# USB-C_Power_Supply.net
KiCad netlist of a schematic drawn in Altium Designer
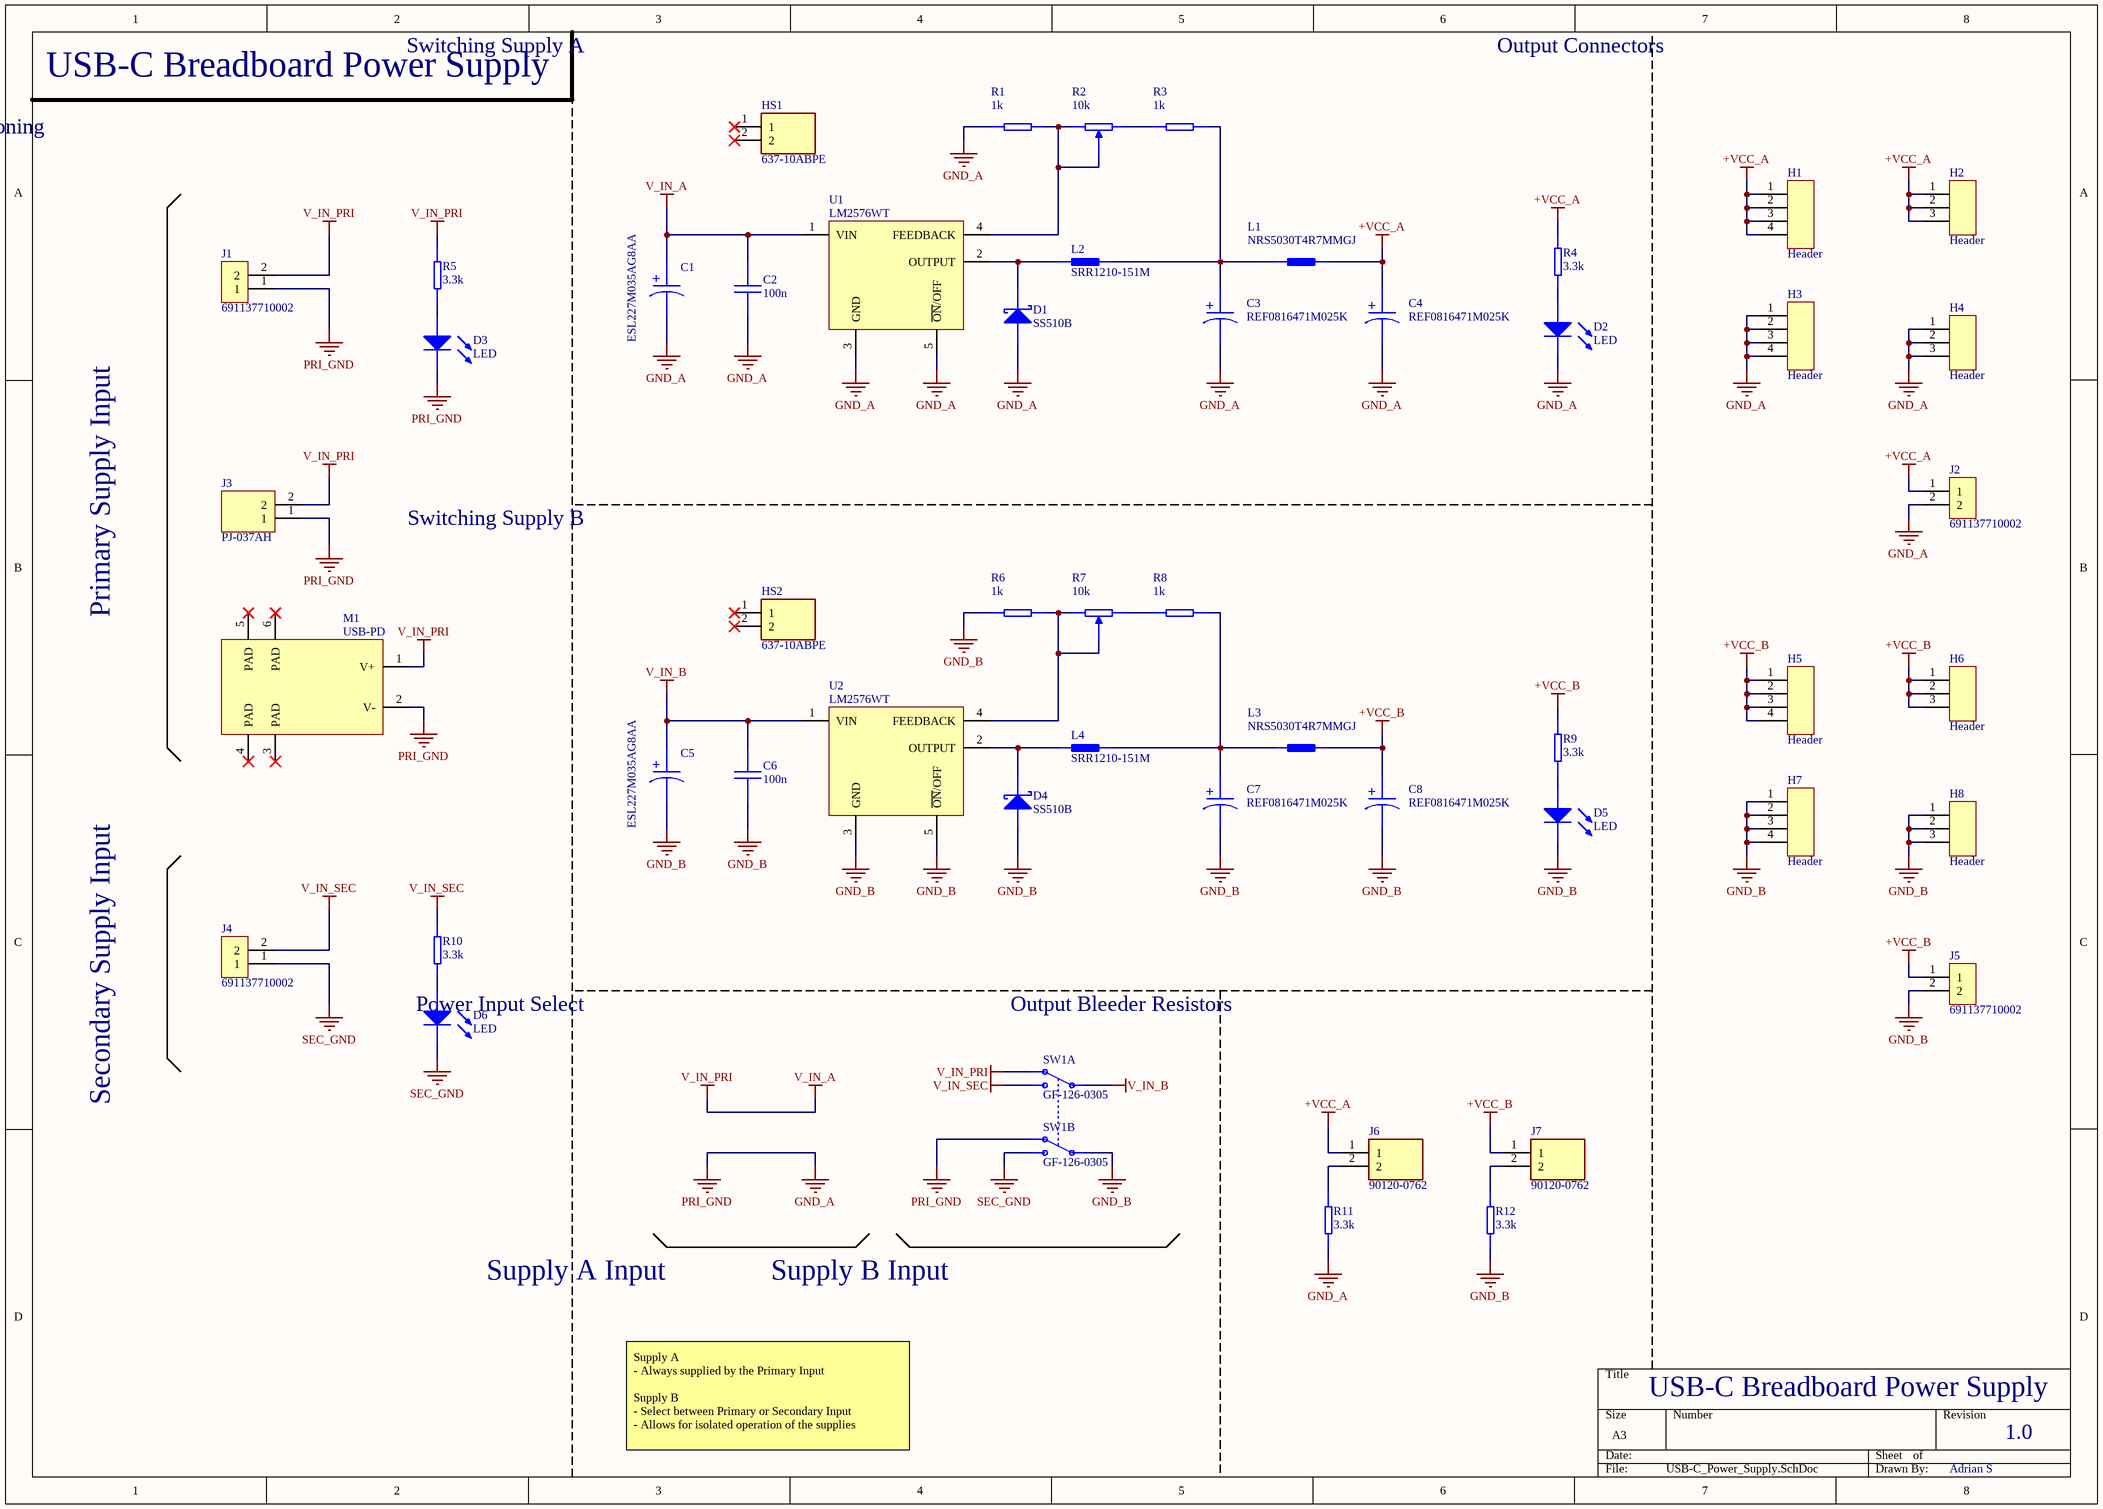
[diagram p0: USB-C_Power_Supply.SchDoc]

(export (version "E")
  (design (tool "Eeschema 10.0.6"))
  (components
    (comp (ref "C1")
      (value "ESL227M035AG8AA")
      (footprint "CAPTH8.00X18.00-3.50")
      (description "Capacitor Polarised")
      (fields (field (name "MOUSER PART NUMBER") "80-ESL227M035AG8AA"))
      (libsource (lib "TD") (part "ESL227M035AG8AA"))
    )
    (comp (ref "C2")
      (value "100n")
      (footprint "CAP0805")
      (description "Non Polarized Capacitor")
      (libsource (lib "TD") (part "Capacitor - Non Polarized"))
    )
    (comp (ref "C3")
      (value "REF0816471M025K")
      (footprint "CAPTH8.00X16.00-3.50")
      (description "Capacitor Polarised")
      (fields (field (name "MOUSER PART NUMBER") "581-REF0816471M025K"))
      (libsource (lib "TD") (part "REF0816471M025K"))
    )
    (comp (ref "C4")
      (value "REF0816471M025K")
      (footprint "CAPTH8.00X16.00-3.50")
      (description "Capacitor Polarised")
      (fields (field (name "MOUSER PART NUMBER") "581-REF0816471M025K"))
      (libsource (lib "TD") (part "REF0816471M025K"))
    )
    (comp (ref "C5")
      (value "ESL227M035AG8AA")
      (footprint "CAPTH8.00X18.00-3.50")
      (description "Capacitor Polarised")
      (fields (field (name "MOUSER PART NUMBER") "80-ESL227M035AG8AA"))
      (libsource (lib "TD") (part "ESL227M035AG8AA"))
    )
    (comp (ref "C6")
      (value "100n")
      (footprint "CAP0805")
      (description "Non Polarized Capacitor")
      (libsource (lib "TD") (part "Capacitor - Non Polarized"))
    )
    (comp (ref "C7")
      (value "REF0816471M025K")
      (footprint "CAPTH8.00X16.00-3.50")
      (description "Capacitor Polarised")
      (fields (field (name "MOUSER PART NUMBER") "581-REF0816471M025K"))
      (libsource (lib "TD") (part "REF0816471M025K"))
    )
    (comp (ref "C8")
      (value "REF0816471M025K")
      (footprint "CAPTH8.00X16.00-3.50")
      (description "Capacitor Polarised")
      (fields (field (name "MOUSER PART NUMBER") "581-REF0816471M025K"))
      (libsource (lib "TD") (part "REF0816471M025K"))
    )
    (comp (ref "D1")
      (value "SS510B")
      (footprint "DO-214AC (SMA)")
      (description "Diode")
      (libsource (lib "TD") (part "SS510B"))
    )
    (comp (ref "D2")
      (value "LED")
      (footprint "LEDM2012X80N")
      (description "General Purpose LED")
      (libsource (lib "TD") (part "LED"))
    )
    (comp (ref "D3")
      (value "LED")
      (footprint "LEDM2012X80N")
      (description "General Purpose LED")
      (libsource (lib "TD") (part "LED"))
    )
    (comp (ref "D4")
      (value "SS510B")
      (footprint "DO-214AC (SMA)")
      (description "Diode")
      (libsource (lib "TD") (part "SS510B"))
    )
    (comp (ref "D5")
      (value "LED")
      (footprint "LEDM2012X80N")
      (description "General Purpose LED")
      (libsource (lib "TD") (part "LED"))
    )
    (comp (ref "D6")
      (value "LED")
      (footprint "LEDM2012X80N")
      (description "General Purpose LED")
      (libsource (lib "TD") (part "LED"))
    )
    (comp (ref "H1")
      (value "Header")
      (footprint "Header_1X4")
      (description "4-Pin Header")
      (libsource (lib "TD") (part "4-Pin Header"))
    )
    (comp (ref "H2")
      (value "Header")
      (footprint "Header_1X3")
      (description "3-Pin Header")
      (libsource (lib "TD") (part "3-Pin Header"))
    )
    (comp (ref "H3")
      (value "Header")
      (footprint "Header_1X4")
      (description "4-Pin Header")
      (libsource (lib "TD") (part "4-Pin Header"))
    )
    (comp (ref "H4")
      (value "Header")
      (footprint "Header_1X3")
      (description "3-Pin Header")
      (libsource (lib "TD") (part "3-Pin Header"))
    )
    (comp (ref "H5")
      (value "Header")
      (footprint "Header_1X4")
      (description "4-Pin Header")
      (libsource (lib "TD") (part "4-Pin Header"))
    )
    (comp (ref "H6")
      (value "Header")
      (footprint "Header_1X3")
      (description "3-Pin Header")
      (libsource (lib "TD") (part "3-Pin Header"))
    )
    (comp (ref "H7")
      (value "Header")
      (footprint "Header_1X4")
      (description "4-Pin Header")
      (libsource (lib "TD") (part "4-Pin Header"))
    )
    (comp (ref "H8")
      (value "Header")
      (footprint "Header_1X3")
      (description "3-Pin Header")
      (libsource (lib "TD") (part "3-Pin Header"))
    )
    (comp (ref "HS1")
      (value "637-10ABPE")
      (footprint "63710ABPE")
      (description "Undefined or Miscellaneous")
      (fields (field (name "MOUSER PART NUMBER") "567-637-10ABPE"))
      (libsource (lib "*") (part "637-10ABPE"))
    )
    (comp (ref "HS2")
      (value "637-10ABPE")
      (footprint "63710ABPE")
      (description "Undefined or Miscellaneous")
      (fields (field (name "MOUSER PART NUMBER") "567-637-10ABPE"))
      (libsource (lib "*") (part "637-10ABPE"))
    )
    (comp (ref "J1")
      (value "691137710002")
      (footprint "SHDR2W70P0X500_1X2_1000X750X1160P")
      (description "Connector")
      (fields (field (name "MOUSER PART NUMBER") "710-691137710002"))
      (libsource (lib "") (part "691137710002_1"))
    )
    (comp (ref "J2")
      (value "691137710002")
      (footprint "SHDR2W70P0X500_1X2_1000X750X1160P")
      (description "Connector")
      (fields (field (name "MOUSER PART NUMBER") "710-691137710002"))
      (libsource (lib "TD") (part "691137710002"))
    )
    (comp (ref "J3")
      (value "PJ-037AH")
      (footprint "PJ037AH")
      (description "Connector")
      (fields (field (name "MOUSER PART NUMBER") "490-PJ-037AH"))
      (libsource (lib "TD") (part "PJ-037AH"))
    )
    (comp (ref "J4")
      (value "691137710002")
      (footprint "SHDR2W70P0X500_1X2_1000X750X1160P")
      (description "Connector")
      (fields (field (name "MOUSER PART NUMBER") "710-691137710002"))
      (libsource (lib "") (part "691137710002_1"))
    )
    (comp (ref "J5")
      (value "691137710002")
      (footprint "SHDR2W70P0X500_1X2_1000X750X1160P")
      (description "Connector")
      (fields (field (name "MOUSER PART NUMBER") "710-691137710002"))
      (libsource (lib "TD") (part "691137710002"))
    )
    (comp (ref "J6")
      (value "90120-0762")
      (footprint "Header_1X2")
      (description "Connector")
      (fields (field (name "MOUSER PART NUMBER") "538-90120-0762"))
      (libsource (lib "SamacSys") (part "90120-0762"))
    )
    (comp (ref "J7")
      (value "90120-0762")
      (footprint "Header_1X2")
      (description "Connector")
      (fields (field (name "MOUSER PART NUMBER") "538-90120-0762"))
      (libsource (lib "SamacSys") (part "90120-0762"))
    )
    (comp (ref "L1")
      (value "NRS5030T4R7MMGJ")
      (footprint "IND (4.9mmx4.9mm)")
      (description "Inductor")
      (fields (field (name "MOUSER PART NUMBER") "963-NRS5030T4R7MMGJ"))
      (libsource (lib "TD") (part "NRS5030T4R7MMGJ"))
    )
    (comp (ref "L2")
      (value "SRR1210-151M")
      (footprint "INDPM120120X1000N-D")
      (description "Inductor")
      (fields (field (name "MOUSER PART NUMBER") "652-SRR1210-151M"))
      (libsource (lib "TD") (part "SRR1210-151M"))
    )
    (comp (ref "L3")
      (value "NRS5030T4R7MMGJ")
      (footprint "IND (4.9mmx4.9mm)")
      (description "Inductor")
      (fields (field (name "MOUSER PART NUMBER") "963-NRS5030T4R7MMGJ"))
      (libsource (lib "TD") (part "NRS5030T4R7MMGJ"))
    )
    (comp (ref "L4")
      (value "SRR1210-151M")
      (footprint "INDPM120120X1000N-D")
      (description "Inductor")
      (fields (field (name "MOUSER PART NUMBER") "652-SRR1210-151M"))
      (libsource (lib "TD") (part "SRR1210-151M"))
    )
    (comp (ref "M1")
      (value "USB-PD")
      (footprint "USB_C-PD")
      (libsource (lib "IEEE_Workshop_SCH") (part "USB-PD"))
    )
    (comp (ref "R1")
      (value "1k")
      (footprint "RESC0805")
      (description "Resistor")
      (libsource (lib "TD") (part "Resistor"))
    )
    (comp (ref "R2")
      (value "10k")
      (footprint "3339P1103LF - Modified")
      (description "Potentionmeter")
      (libsource (lib "TD") (part "Potentiometer"))
    )
    (comp (ref "R3")
      (value "1k")
      (footprint "RESC0805")
      (description "Resistor")
      (libsource (lib "TD") (part "Resistor"))
    )
    (comp (ref "R4")
      (value "3.3k")
      (footprint "RESC0805")
      (description "Resistor")
      (libsource (lib "TD") (part "Resistor"))
    )
    (comp (ref "R5")
      (value "3.3k")
      (footprint "RESC0805")
      (description "Resistor")
      (libsource (lib "TD") (part "Resistor"))
    )
    (comp (ref "R6")
      (value "1k")
      (footprint "RESC0805")
      (description "Resistor")
      (libsource (lib "TD") (part "Resistor"))
    )
    (comp (ref "R7")
      (value "10k")
      (footprint "3339P1103LF - Modified")
      (description "Potentionmeter")
      (libsource (lib "TD") (part "Potentiometer"))
    )
    (comp (ref "R8")
      (value "1k")
      (footprint "RESC0805")
      (description "Resistor")
      (libsource (lib "TD") (part "Resistor"))
    )
    (comp (ref "R9")
      (value "3.3k")
      (footprint "RESC0805")
      (description "Resistor")
      (libsource (lib "TD") (part "Resistor"))
    )
    (comp (ref "R10")
      (value "3.3k")
      (footprint "RESC0805")
      (description "Resistor")
      (libsource (lib "TD") (part "Resistor"))
    )
    (comp (ref "R11")
      (value "3.3k")
      (footprint "RESC0805")
      (description "Resistor")
      (libsource (lib "TD") (part "Resistor"))
    )
    (comp (ref "R12")
      (value "3.3k")
      (footprint "RESC0805")
      (description "Resistor")
      (libsource (lib "TD") (part "Resistor"))
    )
    (comp (ref "SW1")
      (value "GF-126-0305")
      (footprint "GF1260305")
      (description "DPDT Slide Switch")
      (libsource (lib "") (part "GF-126-0305_1"))
    )
    (comp (ref "U1")
      (value "LM2576WT")
      (footprint "TO-220-5")
      (description "Integrated Circuit")
      (fields
        (field (name "MANUFACTURER_PART_NUMBER") "LM2576WU-TR")
        (field (name "MOUSER PART NUMBER") "998-LM2576WT")
      )
      (libsource (lib "TD") (part "LM2576WT"))
    )
    (comp (ref "U2")
      (value "LM2576WT")
      (footprint "TO-220-5")
      (description "Integrated Circuit")
      (fields
        (field (name "MANUFACTURER_PART_NUMBER") "LM2576WU-TR")
        (field (name "MOUSER PART NUMBER") "998-LM2576WT")
      )
      (libsource (lib "TD") (part "LM2576WT"))
    )
  )
  (nets
    (net (code "1") (name "+VCC_A") (class "Default")
      (node (ref "C4") (pin "1") (pintype "passive"))
      (node (ref "H1") (pin "1") (pintype "passive"))
      (node (ref "H1") (pin "2") (pintype "passive"))
      (node (ref "H1") (pin "3") (pintype "passive"))
      (node (ref "H1") (pin "4") (pintype "passive"))
      (node (ref "H2") (pin "1") (pintype "passive"))
      (node (ref "H2") (pin "2") (pintype "passive"))
      (node (ref "H2") (pin "3") (pintype "passive"))
      (node (ref "J2") (pin "1") (pinfunction "1_1") (pintype "passive"))
      (node (ref "J6") (pin "1") (pinfunction "1_1") (pintype "passive"))
      (node (ref "L1") (pin "2") (pintype "passive"))
      (node (ref "R4") (pin "1") (pintype "passive"))
    )
    (net (code "2") (name "+VCC_B") (class "Default")
      (node (ref "C8") (pin "1") (pintype "passive"))
      (node (ref "H5") (pin "1") (pintype "passive"))
      (node (ref "H5") (pin "2") (pintype "passive"))
      (node (ref "H5") (pin "3") (pintype "passive"))
      (node (ref "H5") (pin "4") (pintype "passive"))
      (node (ref "H6") (pin "1") (pintype "passive"))
      (node (ref "H6") (pin "2") (pintype "passive"))
      (node (ref "H6") (pin "3") (pintype "passive"))
      (node (ref "J5") (pin "1") (pinfunction "1_1") (pintype "passive"))
      (node (ref "J7") (pin "1") (pinfunction "1_1") (pintype "passive"))
      (node (ref "L3") (pin "2") (pintype "passive"))
      (node (ref "R9") (pin "1") (pintype "passive"))
    )
    (net (code "3") (name "GND_A") (class "Default")
      (node (ref "C1") (pin "2") (pintype "passive"))
      (node (ref "C2") (pin "2") (pintype "passive"))
      (node (ref "C3") (pin "2") (pintype "passive"))
      (node (ref "C4") (pin "2") (pintype "passive"))
      (node (ref "D1") (pin "2") (pinfunction "A_2") (pintype "passive"))
      (node (ref "D2") (pin "1") (pinfunction "K_1") (pintype "passive"))
      (node (ref "D3") (pin "1") (pinfunction "K_1") (pintype "passive"))
      (node (ref "H3") (pin "1") (pintype "passive"))
      (node (ref "H3") (pin "2") (pintype "passive"))
      (node (ref "H3") (pin "3") (pintype "passive"))
      (node (ref "H3") (pin "4") (pintype "passive"))
      (node (ref "H4") (pin "1") (pintype "passive"))
      (node (ref "H4") (pin "2") (pintype "passive"))
      (node (ref "H4") (pin "3") (pintype "passive"))
      (node (ref "J1") (pin "1") (pinfunction "1_1") (pintype "passive"))
      (node (ref "J2") (pin "2") (pinfunction "2_2") (pintype "passive"))
      (node (ref "J3") (pin "1") (pinfunction "1_1") (pintype "passive"))
      (node (ref "M1") (pin "2") (pinfunction "V-_2") (pintype "passive"))
      (node (ref "R1") (pin "2") (pintype "passive"))
      (node (ref "R11") (pin "2") (pintype "passive"))
      (node (ref "SW1") (pin "6") (pintype "passive"))
      (node (ref "U1") (pin "3") (pinfunction "GND_3") (pintype "passive"))
      (node (ref "U1") (pin "5") (pinfunction "~{ON}/OFF_5") (pintype "passive"))
    )
    (net (code "4") (name "GND_B") (class "Default")
      (node (ref "C5") (pin "2") (pintype "passive"))
      (node (ref "C6") (pin "2") (pintype "passive"))
      (node (ref "C7") (pin "2") (pintype "passive"))
      (node (ref "C8") (pin "2") (pintype "passive"))
      (node (ref "D4") (pin "2") (pinfunction "A_2") (pintype "passive"))
      (node (ref "D5") (pin "1") (pinfunction "K_1") (pintype "passive"))
      (node (ref "H7") (pin "1") (pintype "passive"))
      (node (ref "H7") (pin "2") (pintype "passive"))
      (node (ref "H7") (pin "3") (pintype "passive"))
      (node (ref "H7") (pin "4") (pintype "passive"))
      (node (ref "H8") (pin "1") (pintype "passive"))
      (node (ref "H8") (pin "2") (pintype "passive"))
      (node (ref "H8") (pin "3") (pintype "passive"))
      (node (ref "J5") (pin "2") (pinfunction "2_2") (pintype "passive"))
      (node (ref "R12") (pin "2") (pintype "passive"))
      (node (ref "R6") (pin "2") (pintype "passive"))
      (node (ref "SW1") (pin "5") (pintype "passive"))
      (node (ref "U2") (pin "3") (pinfunction "GND_3") (pintype "passive"))
      (node (ref "U2") (pin "5") (pinfunction "~{ON}/OFF_5") (pintype "passive"))
    )
    (net (code "5") (name "Net-(C3-Pad1)") (class "Default")
      (node (ref "C3") (pin "1") (pintype "passive"))
      (node (ref "L1") (pin "1") (pintype "passive"))
      (node (ref "L2") (pin "2") (pintype "passive"))
      (node (ref "R3") (pin "1") (pintype "passive"))
    )
    (net (code "6") (name "Net-(C7-Pad1)") (class "Default")
      (node (ref "C7") (pin "1") (pintype "passive"))
      (node (ref "L3") (pin "1") (pintype "passive"))
      (node (ref "L4") (pin "2") (pintype "passive"))
      (node (ref "R8") (pin "1") (pintype "passive"))
    )
    (net (code "7") (name "Net-(D1-K)") (class "Default")
      (node (ref "D1") (pin "1") (pinfunction "K_1") (pintype "passive"))
      (node (ref "L2") (pin "1") (pintype "passive"))
      (node (ref "U1") (pin "2") (pinfunction "OUTPUT_2") (pintype "passive"))
    )
    (net (code "8") (name "Net-(D2-A)") (class "Default")
      (node (ref "D2") (pin "2") (pinfunction "A_2") (pintype "passive"))
      (node (ref "R4") (pin "2") (pintype "passive"))
    )
    (net (code "9") (name "Net-(D3-A)") (class "Default")
      (node (ref "D3") (pin "2") (pinfunction "A_2") (pintype "passive"))
      (node (ref "R5") (pin "2") (pintype "passive"))
    )
    (net (code "10") (name "Net-(D4-K)") (class "Default")
      (node (ref "D4") (pin "1") (pinfunction "K_1") (pintype "passive"))
      (node (ref "L4") (pin "1") (pintype "passive"))
      (node (ref "U2") (pin "2") (pinfunction "OUTPUT_2") (pintype "passive"))
    )
    (net (code "11") (name "Net-(D5-A)") (class "Default")
      (node (ref "D5") (pin "2") (pinfunction "A_2") (pintype "passive"))
      (node (ref "R9") (pin "2") (pintype "passive"))
    )
    (net (code "12") (name "Net-(D6-A)") (class "Default")
      (node (ref "D6") (pin "2") (pinfunction "A_2") (pintype "passive"))
      (node (ref "R10") (pin "2") (pintype "passive"))
    )
    (net (code "13") (name "Net-(J6-Pad2)") (class "Default")
      (node (ref "J6") (pin "2") (pinfunction "2_2") (pintype "passive"))
      (node (ref "R11") (pin "1") (pintype "passive"))
    )
    (net (code "14") (name "Net-(J7-Pad2)") (class "Default")
      (node (ref "J7") (pin "2") (pinfunction "2_2") (pintype "passive"))
      (node (ref "R12") (pin "1") (pintype "passive"))
    )
    (net (code "15") (name "Net-(R2-Pad1)") (class "Default")
      (node (ref "R2") (pin "1") (pintype "passive"))
      (node (ref "R3") (pin "2") (pintype "passive"))
    )
    (net (code "16") (name "Net-(R7-Pad1)") (class "Default")
      (node (ref "R7") (pin "1") (pintype "passive"))
      (node (ref "R8") (pin "2") (pintype "passive"))
    )
    (net (code "17") (name "Net-(U1-FEEDBACK)") (class "Default")
      (node (ref "R1") (pin "1") (pintype "passive"))
      (node (ref "R2") (pin "2") (pintype "passive"))
      (node (ref "R2") (pin "3") (pintype "passive"))
      (node (ref "U1") (pin "4") (pinfunction "FEEDBACK_4") (pintype "passive"))
    )
    (net (code "18") (name "Net-(U2-FEEDBACK)") (class "Default")
      (node (ref "R6") (pin "1") (pintype "passive"))
      (node (ref "R7") (pin "2") (pintype "passive"))
      (node (ref "R7") (pin "3") (pintype "passive"))
      (node (ref "U2") (pin "4") (pinfunction "FEEDBACK_4") (pintype "passive"))
    )
    (net (code "19") (name "SEC_GND") (class "Default")
      (node (ref "D6") (pin "1") (pinfunction "K_1") (pintype "passive"))
      (node (ref "J4") (pin "1") (pinfunction "1_1") (pintype "passive"))
      (node (ref "SW1") (pin "4") (pintype "passive"))
    )
    (net (code "20") (name "V_IN_A") (class "Default")
      (node (ref "C1") (pin "1") (pintype "passive"))
      (node (ref "C2") (pin "1") (pintype "passive"))
      (node (ref "J1") (pin "2") (pinfunction "2_2") (pintype "passive"))
      (node (ref "J3") (pin "2") (pinfunction "2_2") (pintype "passive"))
      (node (ref "M1") (pin "1") (pinfunction "V+_1") (pintype "passive"))
      (node (ref "R5") (pin "1") (pintype "passive"))
      (node (ref "SW1") (pin "1") (pintype "passive"))
      (node (ref "U1") (pin "1") (pinfunction "VIN_1") (pintype "passive"))
    )
    (net (code "21") (name "V_IN_B") (class "Default")
      (node (ref "C5") (pin "1") (pintype "passive"))
      (node (ref "C6") (pin "1") (pintype "passive"))
      (node (ref "SW1") (pin "2") (pintype "passive"))
      (node (ref "U2") (pin "1") (pinfunction "VIN_1") (pintype "passive"))
    )
    (net (code "22") (name "V_IN_SEC") (class "Default")
      (node (ref "J4") (pin "2") (pinfunction "2_2") (pintype "passive"))
      (node (ref "R10") (pin "1") (pintype "passive"))
      (node (ref "SW1") (pin "3") (pintype "passive"))
    )
    (net (code "23") (name "unconnected-(HS1-Pad1)") (class "Default")
      (node (ref "HS1") (pin "1") (pinfunction "1_1") (pintype "passive+no_connect"))
    )
    (net (code "24") (name "unconnected-(HS1-Pad2)") (class "Default")
      (node (ref "HS1") (pin "2") (pinfunction "2_2") (pintype "passive+no_connect"))
    )
    (net (code "25") (name "unconnected-(HS2-Pad1)") (class "Default")
      (node (ref "HS2") (pin "1") (pinfunction "1_1") (pintype "passive+no_connect"))
    )
    (net (code "26") (name "unconnected-(HS2-Pad2)") (class "Default")
      (node (ref "HS2") (pin "2") (pinfunction "2_2") (pintype "passive+no_connect"))
    )
    (net (code "27") (name "unconnected-(M1-PAD-Pad3)") (class "Default")
      (node (ref "M1") (pin "3") (pinfunction "PAD_3") (pintype "passive+no_connect"))
    )
    (net (code "28") (name "unconnected-(M1-PAD-Pad4)") (class "Default")
      (node (ref "M1") (pin "4") (pinfunction "PAD_4") (pintype "passive+no_connect"))
    )
    (net (code "29") (name "unconnected-(M1-PAD-Pad5)") (class "Default")
      (node (ref "M1") (pin "5") (pinfunction "PAD_5") (pintype "passive+no_connect"))
    )
    (net (code "30") (name "unconnected-(M1-PAD-Pad6)") (class "Default")
      (node (ref "M1") (pin "6") (pinfunction "PAD_6") (pintype "passive+no_connect"))
    )
  )
)
